# Sensor.net
KiCad netlist of a schematic drawn in Altium Designer
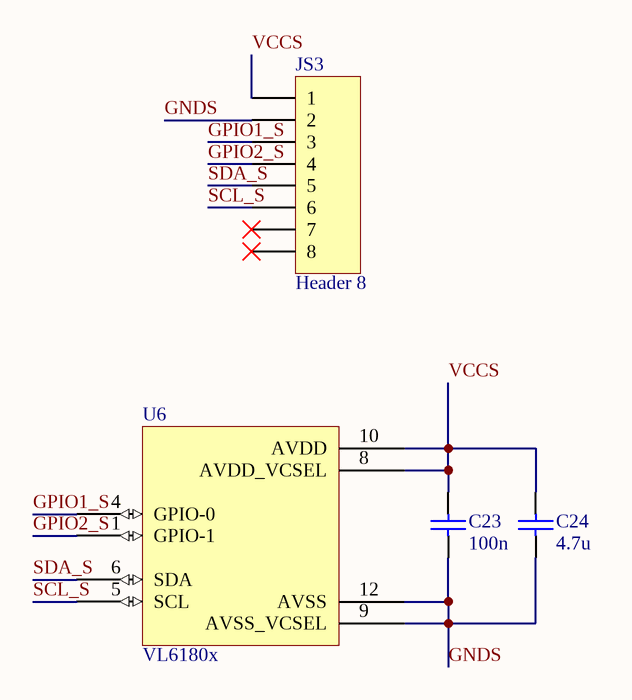
[diagram p0: Sensor.SchDoc]

(export (version "E")
  (design (tool "Eeschema 10.0.6"))
  (components
    (comp (ref "C23")
      (value "100n")
      (footprint "RES 0603/1608")
      (libsource (lib "Miscellaneous Devices") (part "Cap"))
    )
    (comp (ref "C24")
      (value "4.7u")
      (footprint "CAP 0603/1608")
      (libsource (lib "Miscellaneous Devices") (part "Cap"))
    )
    (comp (ref "JS3")
      (value "Header 8")
      (footprint "7-215464-8")
      (libsource (lib "Miscellaneous Connectors") (part "Header 8"))
    )
    (comp (ref "U6") (value "VL6180x") (footprint "LGA12") (libsource (lib "ComponentLib") (part "VL6180x")))
  )
  (nets
    (net (code "1") (name "/GNDS") (class "Default")
      (node (ref "C23") (pin "2") (pinfunction "2_2") (pintype "passive"))
      (node (ref "C24") (pin "1") (pinfunction "1_1") (pintype "passive"))
      (node (ref "JS3") (pin "2") (pinfunction "2_2") (pintype "passive"))
      (node (ref "U6") (pin "12") (pinfunction "AVSS_12") (pintype "power_in"))
      (node (ref "U6") (pin "9") (pinfunction "AVSS_VCSEL_9") (pintype "power_in"))
    )
    (net (code "2") (name "/GPIO1_S") (class "Default")
      (node (ref "JS3") (pin "3") (pinfunction "3_3") (pintype "passive"))
      (node (ref "U6") (pin "4") (pinfunction "GPIO-0_4") (pintype "bidirectional"))
    )
    (net (code "3") (name "/GPIO2_S") (class "Default")
      (node (ref "JS3") (pin "4") (pinfunction "4_4") (pintype "passive"))
      (node (ref "U6") (pin "1") (pinfunction "GPIO-1_1") (pintype "bidirectional"))
    )
    (net (code "4") (name "/SCL_S") (class "Default")
      (node (ref "JS3") (pin "6") (pinfunction "6_6") (pintype "passive"))
      (node (ref "U6") (pin "5") (pinfunction "SCL_5") (pintype "bidirectional"))
    )
    (net (code "5") (name "/SDA_S") (class "Default")
      (node (ref "JS3") (pin "5") (pinfunction "5_5") (pintype "passive"))
      (node (ref "U6") (pin "6") (pinfunction "SDA_6") (pintype "bidirectional"))
    )
    (net (code "6") (name "/VCCS") (class "Default")
      (node (ref "C23") (pin "1") (pinfunction "1_1") (pintype "passive"))
      (node (ref "C24") (pin "2") (pinfunction "2_2") (pintype "passive"))
      (node (ref "JS3") (pin "1") (pinfunction "1_1") (pintype "passive"))
      (node (ref "U6") (pin "10") (pinfunction "AVDD_10") (pintype "power_in"))
      (node (ref "U6") (pin "8") (pinfunction "AVDD_VCSEL_8") (pintype "power_in"))
    )
    (net (code "7") (name "unconnected-(JS3-Pad7)") (class "Default")
      (node (ref "JS3") (pin "7") (pinfunction "7_7") (pintype "passive+no_connect"))
    )
    (net (code "8") (name "unconnected-(JS3-Pad8)") (class "Default")
      (node (ref "JS3") (pin "8") (pinfunction "8_8") (pintype "passive+no_connect"))
    )
  )
)
